# inp.net
KiCad netlist of a schematic drawn in EAGLE
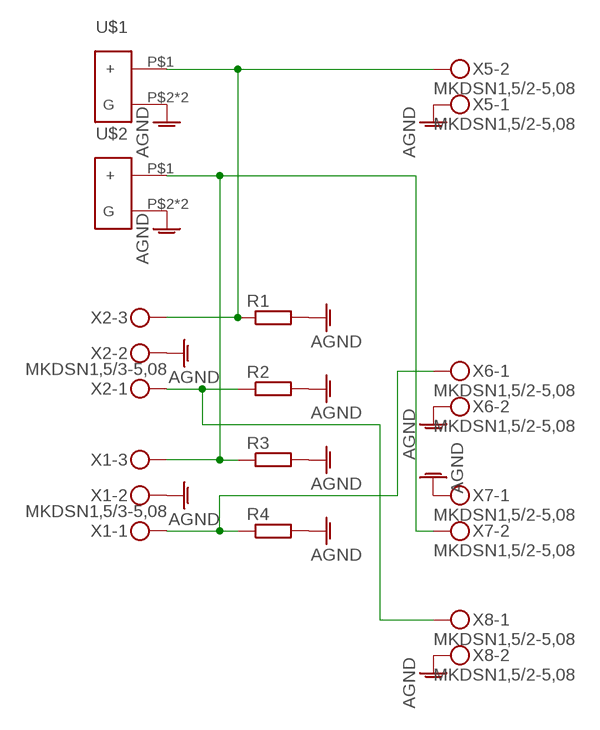
[diagram p0: schematic, sheet 1]

(export (version "E")
  (design (tool "Eeschema 10.0.6"))
  (components
    (comp (ref "R1")
      (value "R-EU_MELF0204W")
      (footprint "eagle-import:MINI_MELF-0204W")
      (libsource (lib "eagle-import") (part "R-EU_MELF0204W"))
    )
    (comp (ref "R2")
      (value "R-EU_MELF0204W")
      (footprint "eagle-import:MINI_MELF-0204W")
      (libsource (lib "eagle-import") (part "R-EU_MELF0204W"))
    )
    (comp (ref "R3")
      (value "R-EU_MELF0204W")
      (footprint "eagle-import:MINI_MELF-0204W")
      (libsource (lib "eagle-import") (part "R-EU_MELF0204W"))
    )
    (comp (ref "R4")
      (value "R-EU_MELF0204W")
      (footprint "eagle-import:MINI_MELF-0204W")
      (libsource (lib "eagle-import") (part "R-EU_MELF0204W"))
    )
    (comp (ref "U$1")
      (value "MSRCA")
      (footprint "eagle-import:MSRCA")
      (libsource (lib "eagle-import") (part "MSRCA"))
    )
    (comp (ref "U$2")
      (value "MSRCA")
      (footprint "eagle-import:MSRCA")
      (libsource (lib "eagle-import") (part "MSRCA"))
    )
    (comp (ref "X1")
      (value "MKDSN1,5/3-5,08")
      (footprint "eagle-import:MKDSN1,5_3-5,08")
      (libsource (lib "eagle-import") (part "MKDSN1,5/3-5,08"))
    )
    (comp (ref "X2")
      (value "MKDSN1,5/3-5,08")
      (footprint "eagle-import:MKDSN1,5_3-5,08")
      (libsource (lib "eagle-import") (part "MKDSN1,5/3-5,08"))
    )
    (comp (ref "X5")
      (value "MKDSN1,5/2-5,08")
      (footprint "eagle-import:MKDSN1,5_2-5,08")
      (libsource (lib "eagle-import") (part "MKDSN1,5/2-5,08"))
    )
    (comp (ref "X6")
      (value "MKDSN1,5/2-5,08")
      (footprint "eagle-import:MKDSN1,5_2-5,08")
      (libsource (lib "eagle-import") (part "MKDSN1,5/2-5,08"))
    )
    (comp (ref "X7")
      (value "MKDSN1,5/2-5,08")
      (footprint "eagle-import:MKDSN1,5_2-5,08")
      (libsource (lib "eagle-import") (part "MKDSN1,5/2-5,08"))
    )
    (comp (ref "X8")
      (value "MKDSN1,5/2-5,08")
      (footprint "eagle-import:MKDSN1,5_2-5,08")
      (libsource (lib "eagle-import") (part "MKDSN1,5/2-5,08"))
    )
  )
  (nets
    (net (code "1") (name "AGND") (class "Default")
      (node (ref "R1") (pin "2") (pinfunction "2_2") (pintype "passive"))
      (node (ref "R2") (pin "2") (pinfunction "2_2") (pintype "passive"))
      (node (ref "R3") (pin "2") (pinfunction "2_2") (pintype "passive"))
      (node (ref "R4") (pin "2") (pinfunction "2_2") (pintype "passive"))
      (node (ref "U$1") (pin "P$2") (pinfunction "G_P$2") (pintype "bidirectional"))
      (node (ref "U$1") (pin "P$3") (pinfunction "G_P$3") (pintype "bidirectional"))
      (node (ref "U$2") (pin "P$2") (pinfunction "G_P$2") (pintype "bidirectional"))
      (node (ref "U$2") (pin "P$3") (pinfunction "G_P$3") (pintype "bidirectional"))
      (node (ref "X1") (pin "2") (pinfunction "KL_2") (pintype "passive"))
      (node (ref "X2") (pin "2") (pinfunction "KL_2") (pintype "passive"))
      (node (ref "X5") (pin "1") (pinfunction "KL_1") (pintype "passive"))
      (node (ref "X6") (pin "2") (pinfunction "KL_2") (pintype "passive"))
      (node (ref "X7") (pin "1") (pinfunction "KL_1") (pintype "passive"))
      (node (ref "X8") (pin "2") (pinfunction "KL_2") (pintype "passive"))
    )
    (net (code "2") (name "Net-(U$1-+)") (class "Default")
      (node (ref "R1") (pin "1") (pinfunction "1_1") (pintype "passive"))
      (node (ref "U$1") (pin "P$1") (pinfunction "+_P$1") (pintype "bidirectional"))
      (node (ref "X2") (pin "3") (pinfunction "KL_3") (pintype "passive"))
      (node (ref "X5") (pin "2") (pinfunction "KL_2") (pintype "passive"))
    )
    (net (code "3") (name "Net-(U$2-+)") (class "Default")
      (node (ref "R3") (pin "1") (pinfunction "1_1") (pintype "passive"))
      (node (ref "U$2") (pin "P$1") (pinfunction "+_P$1") (pintype "bidirectional"))
      (node (ref "X1") (pin "3") (pinfunction "KL_3") (pintype "passive"))
      (node (ref "X7") (pin "2") (pinfunction "KL_2") (pintype "passive"))
    )
    (net (code "4") (name "Net-(X1A-KL)") (class "Default")
      (node (ref "R4") (pin "1") (pinfunction "1_1") (pintype "passive"))
      (node (ref "X1") (pin "1") (pinfunction "KL_1") (pintype "passive"))
      (node (ref "X6") (pin "1") (pinfunction "KL_1") (pintype "passive"))
    )
    (net (code "5") (name "Net-(X2A-KL)") (class "Default")
      (node (ref "R2") (pin "1") (pinfunction "1_1") (pintype "passive"))
      (node (ref "X2") (pin "1") (pinfunction "KL_1") (pintype "passive"))
      (node (ref "X8") (pin "1") (pinfunction "KL_1") (pintype "passive"))
    )
  )
)
